# ATtinyRTCSwitch.net
KiCad netlist of a schematic drawn in EAGLE
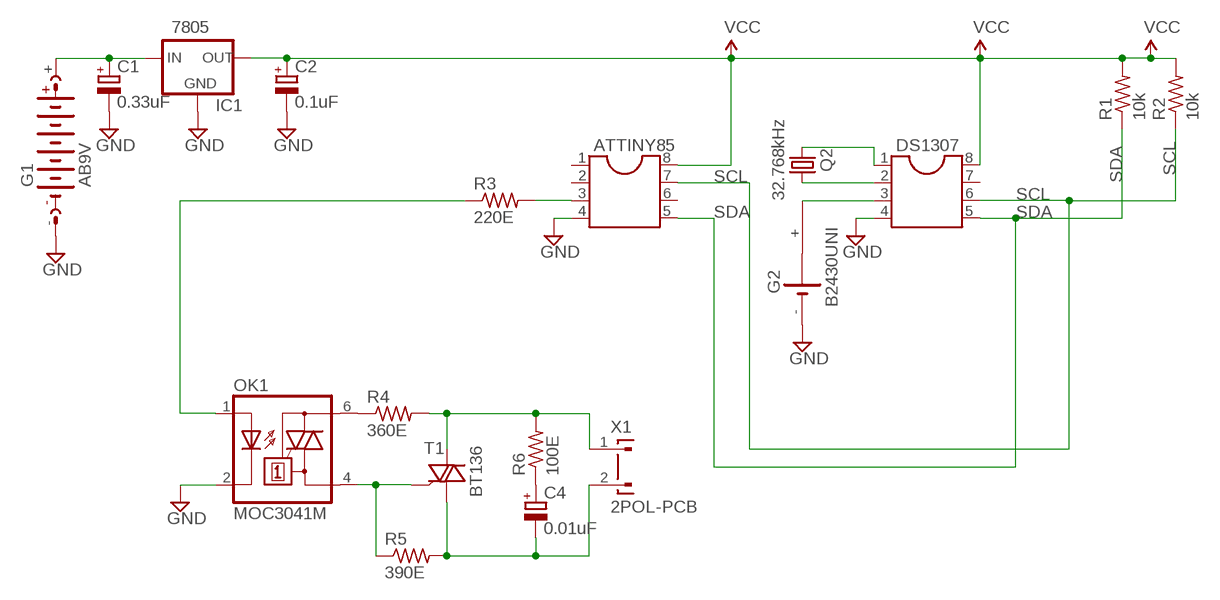
[diagram p0: schematic, sheet 1]

(export (version "E")
  (design (tool "Eeschema 10.0.6"))
  (components
    (comp (ref "ATTINY85")
      (value "DIL8")
      (footprint "eagle-import:DIL08")
      (libsource (lib "eagle-import") (part "DIL8"))
    )
    (comp (ref "C1")
      (value "0.33uF")
      (footprint "eagle-import:E2,5-5")
      (libsource (lib "eagle-import") (part "CPOL-EUE2.5-5"))
    )
    (comp (ref "C2")
      (value "0.1uF")
      (footprint "eagle-import:E2,5-5")
      (libsource (lib "eagle-import") (part "CPOL-EUE2.5-5"))
    )
    (comp (ref "C4")
      (value "0.01uF")
      (footprint "eagle-import:E2,5-5")
      (libsource (lib "eagle-import") (part "CPOL-EUE2.5-5"))
    )
    (comp (ref "DS1307")
      (value "DIL8")
      (footprint "eagle-import:DIL08")
      (libsource (lib "eagle-import") (part "DIL8"))
    )
    (comp (ref "G1")
      (value "AB9V")
      (footprint "eagle-import:AB9V")
      (libsource (lib "eagle-import") (part "AB9V"))
    )
    (comp (ref "G2")
      (value "B2430UNI")
      (footprint "eagle-import:B2430UNI")
      (libsource (lib "eagle-import") (part "B2430UNI"))
    )
    (comp (ref "IC1")
      (value "7805")
      (footprint "eagle-import:78XXL")
      (libsource (lib "eagle-import") (part "V_REG_78XXSIDE"))
    )
    (comp (ref "OK1")
      (value "MOC3041M")
      (footprint "eagle-import:DIL06")
      (fields (field (name "MF") "FAIRCHILD SEMICONDUCTOR"))
      (libsource (lib "eagle-import") (part "MOC3041M"))
    )
    (comp (ref "Q2")
      (value "32.768kHz")
      (footprint "eagle-import:TC26H")
      (libsource (lib "eagle-import") (part "CRYSTALTC26H"))
    )
    (comp (ref "R1")
      (value "10k")
      (footprint "eagle-import:0204_7")
      (libsource (lib "eagle-import") (part "R-US_0204/7"))
    )
    (comp (ref "R2")
      (value "10k")
      (footprint "eagle-import:0204_7")
      (libsource (lib "eagle-import") (part "R-US_0204/7"))
    )
    (comp (ref "R3")
      (value "220E")
      (footprint "eagle-import:0204_7")
      (libsource (lib "eagle-import") (part "R-US_0204/7"))
    )
    (comp (ref "R4")
      (value "360E")
      (footprint "eagle-import:0204_7")
      (libsource (lib "eagle-import") (part "R-US_0204/7"))
    )
    (comp (ref "R5")
      (value "390E")
      (footprint "eagle-import:0204_7")
      (libsource (lib "eagle-import") (part "R-US_0204/7"))
    )
    (comp (ref "R6")
      (value "100E")
      (footprint "eagle-import:0204_7")
      (libsource (lib "eagle-import") (part "R-US_0204/7"))
    )
    (comp (ref "T1")
      (value "BT136")
      (footprint "eagle-import:TO220AB")
      (libsource (lib "eagle-import") (part "BT136"))
    )
    (comp (ref "X1")
      (value "2POL-PCB")
      (footprint "eagle-import:2POL-PCB")
      (libsource (lib "eagle-import") (part "2POL-PCB"))
    )
  )
  (nets
    (net (code "1") (name "/SCL") (class "Default")
      (node (ref "ATTINY85") (pin "7") (pinfunction "7_7") (pintype "passive"))
      (node (ref "DS1307") (pin "6") (pinfunction "6_6") (pintype "passive"))
      (node (ref "R2") (pin "1") (pinfunction "1_1") (pintype "passive"))
    )
    (net (code "2") (name "/SDA") (class "Default")
      (node (ref "ATTINY85") (pin "5") (pinfunction "5_5") (pintype "passive"))
      (node (ref "DS1307") (pin "5") (pinfunction "5_5") (pintype "passive"))
      (node (ref "R1") (pin "1") (pinfunction "1_1") (pintype "passive"))
    )
    (net (code "3") (name "GND") (class "Default")
      (node (ref "ATTINY85") (pin "4") (pinfunction "4_4") (pintype "passive"))
      (node (ref "C1") (pin "-") (pinfunction "-_-") (pintype "passive"))
      (node (ref "C2") (pin "-") (pinfunction "-_-") (pintype "passive"))
      (node (ref "DS1307") (pin "4") (pinfunction "4_4") (pintype "passive"))
      (node (ref "G1") (pin "-") (pinfunction "-_-") (pintype "passive"))
      (node (ref "G2") (pin "-") (pinfunction "-_-") (pintype "passive"))
      (node (ref "IC1") (pin "GND") (pinfunction "GND_GND") (pintype "input"))
      (node (ref "OK1") (pin "2") (pinfunction "C_2") (pintype "passive"))
    )
    (net (code "4") (name "Net-(ATTINY85-Pad3)") (class "Default")
      (node (ref "ATTINY85") (pin "3") (pinfunction "3_3") (pintype "passive"))
      (node (ref "R3") (pin "2") (pinfunction "2_2") (pintype "passive"))
    )
    (net (code "5") (name "Net-(C1-Pad+)") (class "Default")
      (node (ref "C1") (pin "+") (pinfunction "+_+") (pintype "passive"))
      (node (ref "G1") (pin "+") (pinfunction "+_+") (pintype "passive"))
      (node (ref "IC1") (pin "IN") (pinfunction "IN_IN") (pintype "input"))
    )
    (net (code "6") (name "Net-(C4-Pad+)") (class "Default")
      (node (ref "C4") (pin "+") (pinfunction "+_+") (pintype "passive"))
      (node (ref "R6") (pin "1") (pinfunction "1_1") (pintype "passive"))
    )
    (net (code "7") (name "Net-(DS1307-Pad1)") (class "Default")
      (node (ref "DS1307") (pin "1") (pinfunction "1_1") (pintype "passive"))
      (node (ref "Q2") (pin "2") (pinfunction "2_2") (pintype "passive"))
    )
    (net (code "8") (name "Net-(DS1307-Pad2)") (class "Default")
      (node (ref "DS1307") (pin "2") (pinfunction "2_2") (pintype "passive"))
      (node (ref "Q2") (pin "1") (pinfunction "1_1") (pintype "passive"))
    )
    (net (code "9") (name "Net-(DS1307-Pad3)") (class "Default")
      (node (ref "DS1307") (pin "3") (pinfunction "3_3") (pintype "passive"))
      (node (ref "G2") (pin "+") (pinfunction "+_+") (pintype "passive"))
    )
    (net (code "10") (name "Net-(OK1-A)") (class "Default")
      (node (ref "OK1") (pin "1") (pinfunction "A_1") (pintype "passive"))
      (node (ref "R3") (pin "1") (pinfunction "1_1") (pintype "passive"))
    )
    (net (code "11") (name "Net-(OK1-A1)") (class "Default")
      (node (ref "OK1") (pin "4") (pinfunction "A1_4") (pintype "passive"))
      (node (ref "R5") (pin "1") (pinfunction "1_1") (pintype "passive"))
      (node (ref "T1") (pin "3") (pinfunction "G_3") (pintype "passive"))
    )
    (net (code "12") (name "Net-(OK1-A2)") (class "Default")
      (node (ref "OK1") (pin "6") (pinfunction "A2_6") (pintype "passive"))
      (node (ref "R4") (pin "1") (pinfunction "1_1") (pintype "passive"))
    )
    (net (code "13") (name "Net-(T1-A1)") (class "Default")
      (node (ref "C4") (pin "-") (pinfunction "-_-") (pintype "passive"))
      (node (ref "R5") (pin "2") (pinfunction "2_2") (pintype "passive"))
      (node (ref "T1") (pin "1") (pinfunction "A1_1") (pintype "passive"))
      (node (ref "X1") (pin "2") (pinfunction "2_2") (pintype "passive"))
    )
    (net (code "14") (name "Net-(T1-A2)") (class "Default")
      (node (ref "R4") (pin "2") (pinfunction "2_2") (pintype "passive"))
      (node (ref "R6") (pin "2") (pinfunction "2_2") (pintype "passive"))
      (node (ref "T1") (pin "2") (pinfunction "A2_2") (pintype "passive"))
      (node (ref "X1") (pin "1") (pinfunction "1_1") (pintype "passive"))
    )
    (net (code "15") (name "VCC") (class "Default")
      (node (ref "ATTINY85") (pin "8") (pinfunction "8_8") (pintype "passive"))
      (node (ref "C2") (pin "+") (pinfunction "+_+") (pintype "passive"))
      (node (ref "DS1307") (pin "8") (pinfunction "8_8") (pintype "passive"))
      (node (ref "IC1") (pin "OUT") (pinfunction "OUT_OUT") (pintype "output"))
      (node (ref "R1") (pin "2") (pinfunction "2_2") (pintype "passive"))
      (node (ref "R2") (pin "2") (pinfunction "2_2") (pintype "passive"))
    )
    (net (code "16") (name "unconnected-(ATTINY85-Pad1)") (class "Default")
      (node (ref "ATTINY85") (pin "1") (pinfunction "1_1") (pintype "passive"))
    )
    (net (code "17") (name "unconnected-(ATTINY85-Pad2)") (class "Default")
      (node (ref "ATTINY85") (pin "2") (pinfunction "2_2") (pintype "passive"))
    )
    (net (code "18") (name "unconnected-(ATTINY85-Pad6)") (class "Default")
      (node (ref "ATTINY85") (pin "6") (pinfunction "6_6") (pintype "passive"))
    )
    (net (code "19") (name "unconnected-(DS1307-Pad7)") (class "Default")
      (node (ref "DS1307") (pin "7") (pinfunction "7_7") (pintype "passive"))
    )
    (net (code "20") (name "unconnected-(G2-+-Pad+@1)") (class "Default")
      (node (ref "G2") (pin "+@1") (pinfunction "+_+@1") (pintype "passive"))
    )
    (net (code "21") (name "unconnected-(G2-+-Pad+@2)") (class "Default")
      (node (ref "G2") (pin "+@2") (pinfunction "+_+@2") (pintype "passive"))
    )
    (net (code "22") (name "unconnected-(G2-+-Pad+@3)") (class "Default")
      (node (ref "G2") (pin "+@3") (pinfunction "+_+@3") (pintype "passive"))
    )
    (net (code "23") (name "unconnected-(G2-+-Pad+@4)") (class "Default")
      (node (ref "G2") (pin "+@4") (pinfunction "+_+@4") (pintype "passive"))
    )
    (net (code "24") (name "unconnected-(G2---Pad-@1)") (class "Default")
      (node (ref "G2") (pin "-@1") (pinfunction "-_-@1") (pintype "passive"))
    )
  )
)
